# mcp1824bo.net
KiCad netlist of a schematic drawn in EAGLE
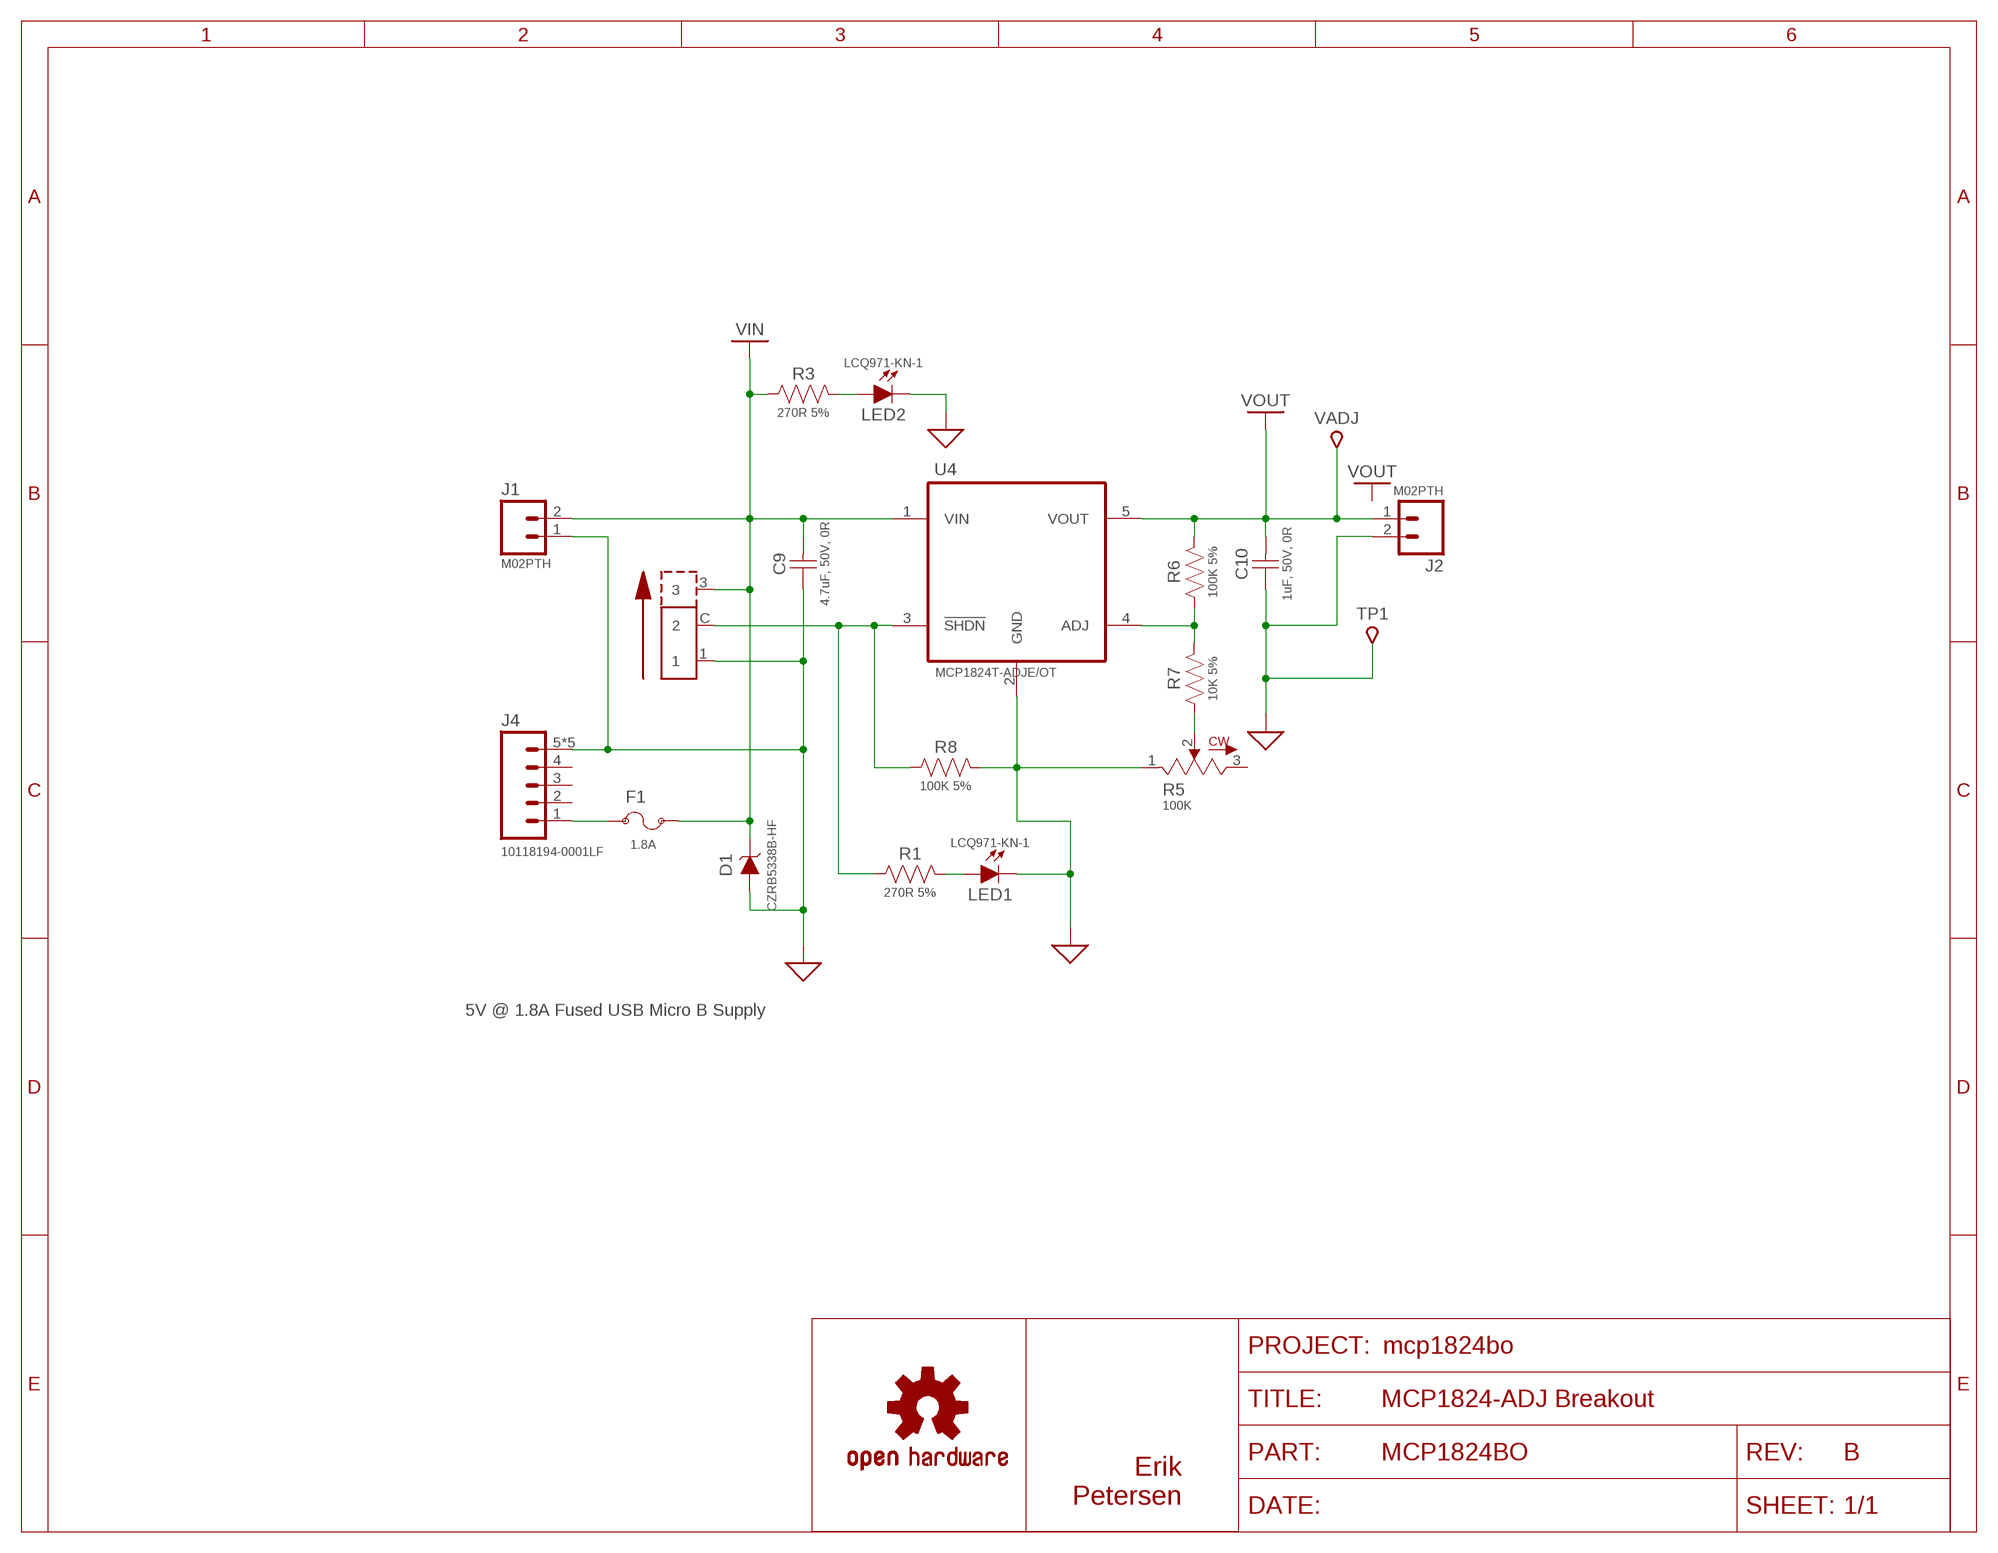
[diagram p0: schematic, sheet 1]

(export (version "E")
  (design (tool "Eeschema 10.0.6"))
  (components
    (comp (ref "C9")
      (value "4.7uF, 50V, 0R")
      (footprint "eagle-import:31-1206")
      (fields (field (name "MANUFACTURER_PART_NUMBER") "GRM31CR71H475KA12L"))
      (libsource (lib "eagle-import") (part "GRM31CR71H475KA12L"))
    )
    (comp (ref "C10")
      (value "1uF, 50V, 0R")
      (footprint "eagle-import:21-0805")
      (fields (field (name "MANUFACTURER_PART_NUMBER") "GRM21BR71H105KA12L"))
      (libsource (lib "eagle-import") (part "GRM21BR71H105KA12L"))
    )
    (comp (ref "D1")
      (value "CZRB5338B-HF")
      (footprint "eagle-import:DO-214AA")
      (libsource (lib "eagle-import") (part "CZRB?B-HF5338"))
    )
    (comp (ref "F1")
      (value "1.8A")
      (footprint "eagle-import:1206")
      (libsource (lib "eagle-import") (part "1206L100"))
    )
    (comp (ref "J1")
      (value "M02PTH")
      (footprint "eagle-import:1X02")
      (libsource (lib "eagle-import") (part "M02PTH"))
    )
    (comp (ref "J2")
      (value "M02PTH")
      (footprint "eagle-import:1X02")
      (libsource (lib "eagle-import") (part "M02PTH"))
    )
    (comp (ref "J4")
      (value "10118194-0001LF")
      (footprint "eagle-import:USB-MICROB")
      (libsource (lib "eagle-import") (part "M05USB-MICRO"))
    )
    (comp (ref "LED1")
      (value "LCQ971-KN-1")
      (footprint "eagle-import:CHIPLED_0603")
      (libsource (lib "eagle-import") (part "LEDCHIPLED_0603"))
    )
    (comp (ref "LED2")
      (value "LCQ971-KN-1")
      (footprint "eagle-import:CHIPLED_0603")
      (libsource (lib "eagle-import") (part "LEDCHIPLED_0603"))
    )
    (comp (ref "LOGO1")
      (value "OSHW-LOGOS")
      (footprint "eagle-import:OSHW-LOGO-S")
      (libsource (lib "eagle-import") (part "OSHW-LOGOS"))
    )
    (comp (ref "R1")
      (value "270R 5%")
      (footprint "eagle-import:R0603")
      (libsource (lib "eagle-import") (part "ERJ-?3GEYJ271"))
    )
    (comp (ref "R3")
      (value "270R 5%")
      (footprint "eagle-import:R0603")
      (libsource (lib "eagle-import") (part "ERJ-?3GEYJ271"))
    )
    (comp (ref "R5")
      (value "100K")
      (footprint "eagle-import:T93YA")
      (libsource (lib "eagle-import") (part "T93?KT20YA104"))
    )
    (comp (ref "R6")
      (value "100K 5%")
      (footprint "eagle-import:R0603")
      (libsource (lib "eagle-import") (part "ERJ-?3GEYJ104"))
    )
    (comp (ref "R7")
      (value "10K 5%")
      (footprint "eagle-import:R0603")
      (libsource (lib "eagle-import") (part "ERJ-?3GEYJ103"))
    )
    (comp (ref "R8")
      (value "100K 5%")
      (footprint "eagle-import:R0603")
      (libsource (lib "eagle-import") (part "ERJ-?3GEYJ104"))
    )
    (comp (ref "SW1")
      (value "CL-SB-12A-01")
      (footprint "eagle-import:CL-SB-12A")
      (libsource (lib "eagle-import") (part "CL-SB-12?-A01"))
    )
    (comp (ref "TP1")
      (value "TP-5001K-040")
      (footprint "eagle-import:TP5000K-040")
      (libsource (lib "eagle-import") (part "TP-50K-?04001"))
    )
    (comp (ref "U4")
      (value "MCP1824T-ADJE/OT")
      (footprint "eagle-import:SOT95P270X145-5N")
      (libsource (lib "eagle-import") (part "MCP1824T-ADJE/OT"))
    )
    (comp (ref "VADJ")
      (value "TP-5000K-040")
      (footprint "eagle-import:TP5000K-040")
      (libsource (lib "eagle-import") (part "TP-50K-?04000"))
    )
  )
  (nets
    (net (code "1") (name "GND") (class "Default")
      (node (ref "C10") (pin "1") (pinfunction "1_1") (pintype "passive"))
      (node (ref "C9") (pin "1") (pinfunction "1_1") (pintype "passive"))
      (node (ref "D1") (pin "A") (pinfunction "A_A") (pintype "passive"))
      (node (ref "J1") (pin "1") (pinfunction "1_1") (pintype "passive"))
      (node (ref "J2") (pin "2") (pinfunction "2_2") (pintype "passive"))
      (node (ref "J4") (pin "5") (pinfunction "5_5") (pintype "passive"))
      (node (ref "J4") (pin "6") (pinfunction "5_6") (pintype "passive"))
      (node (ref "J4") (pin "7") (pinfunction "5_7") (pintype "passive"))
      (node (ref "J4") (pin "8") (pinfunction "5_8") (pintype "passive"))
      (node (ref "J4") (pin "9") (pinfunction "5_9") (pintype "passive"))
      (node (ref "LED1") (pin "C") (pinfunction "C_C") (pintype "passive"))
      (node (ref "LED2") (pin "C") (pinfunction "C_C") (pintype "passive"))
      (node (ref "R5") (pin "1") (pinfunction "1_1") (pintype "passive"))
      (node (ref "R8") (pin "2") (pinfunction "2_2") (pintype "passive"))
      (node (ref "SW1") (pin "1") (pinfunction "1_1") (pintype "passive"))
      (node (ref "TP1") (pin "PP") (pinfunction "PP_PP") (pintype "passive"))
      (node (ref "U4") (pin "2") (pinfunction "GND_2") (pintype "passive"))
    )
    (net (code "2") (name "Net-(F1-Pad1)") (class "Default")
      (node (ref "F1") (pin "1") (pinfunction "1_1") (pintype "passive"))
      (node (ref "J4") (pin "1") (pinfunction "1_1") (pintype "passive"))
    )
    (net (code "3") (name "Net-(LED1-PadA)") (class "Default")
      (node (ref "LED1") (pin "A") (pinfunction "A_A") (pintype "passive"))
      (node (ref "R1") (pin "2") (pinfunction "2_2") (pintype "passive"))
    )
    (net (code "4") (name "Net-(LED2-PadA)") (class "Default")
      (node (ref "LED2") (pin "A") (pinfunction "A_A") (pintype "passive"))
      (node (ref "R3") (pin "2") (pinfunction "2_2") (pintype "passive"))
    )
    (net (code "5") (name "Net-(R5-Pad2)") (class "Default")
      (node (ref "R5") (pin "2") (pinfunction "2_2") (pintype "passive"))
      (node (ref "R7") (pin "1") (pinfunction "1_1") (pintype "passive"))
    )
    (net (code "6") (name "Net-(SW1-2)") (class "Default")
      (node (ref "R1") (pin "1") (pinfunction "1_1") (pintype "passive"))
      (node (ref "R8") (pin "1") (pinfunction "1_1") (pintype "passive"))
      (node (ref "SW1") (pin "C") (pinfunction "2_C") (pintype "passive"))
      (node (ref "U4") (pin "3") (pinfunction "~{SHDN}_3") (pintype "input"))
    )
    (net (code "7") (name "Net-(U4-ADJ)") (class "Default")
      (node (ref "R6") (pin "1") (pinfunction "1_1") (pintype "passive"))
      (node (ref "R7") (pin "2") (pinfunction "2_2") (pintype "passive"))
      (node (ref "U4") (pin "4") (pinfunction "ADJ_4") (pintype "input"))
    )
    (net (code "8") (name "VIN") (class "Default")
      (node (ref "C9") (pin "2") (pinfunction "2_2") (pintype "passive"))
      (node (ref "D1") (pin "C") (pinfunction "C_C") (pintype "passive"))
      (node (ref "F1") (pin "2") (pinfunction "2_2") (pintype "passive"))
      (node (ref "J1") (pin "2") (pinfunction "2_2") (pintype "passive"))
      (node (ref "R3") (pin "1") (pinfunction "1_1") (pintype "passive"))
      (node (ref "SW1") (pin "3") (pinfunction "3_3") (pintype "passive"))
      (node (ref "U4") (pin "1") (pinfunction "VIN_1") (pintype "power_in"))
    )
    (net (code "9") (name "VOUT") (class "Default")
      (node (ref "C10") (pin "2") (pinfunction "2_2") (pintype "passive"))
      (node (ref "J2") (pin "1") (pinfunction "1_1") (pintype "passive"))
      (node (ref "R6") (pin "2") (pinfunction "2_2") (pintype "passive"))
      (node (ref "U4") (pin "5") (pinfunction "VOUT_5") (pintype "power_in"))
      (node (ref "VADJ") (pin "PP") (pinfunction "PP_PP") (pintype "passive"))
    )
    (net (code "10") (name "unconnected-(J4-Pad2)") (class "Default")
      (node (ref "J4") (pin "2") (pinfunction "2_2") (pintype "passive"))
    )
    (net (code "11") (name "unconnected-(J4-Pad3)") (class "Default")
      (node (ref "J4") (pin "3") (pinfunction "3_3") (pintype "passive"))
    )
    (net (code "12") (name "unconnected-(J4-Pad4)") (class "Default")
      (node (ref "J4") (pin "4") (pinfunction "4_4") (pintype "passive"))
    )
    (net (code "13") (name "unconnected-(R5-Pad3)") (class "Default")
      (node (ref "R5") (pin "3") (pinfunction "3_3") (pintype "passive"))
    )
  )
)
